# dongle.net
KiCad netlist of a schematic drawn in EAGLE
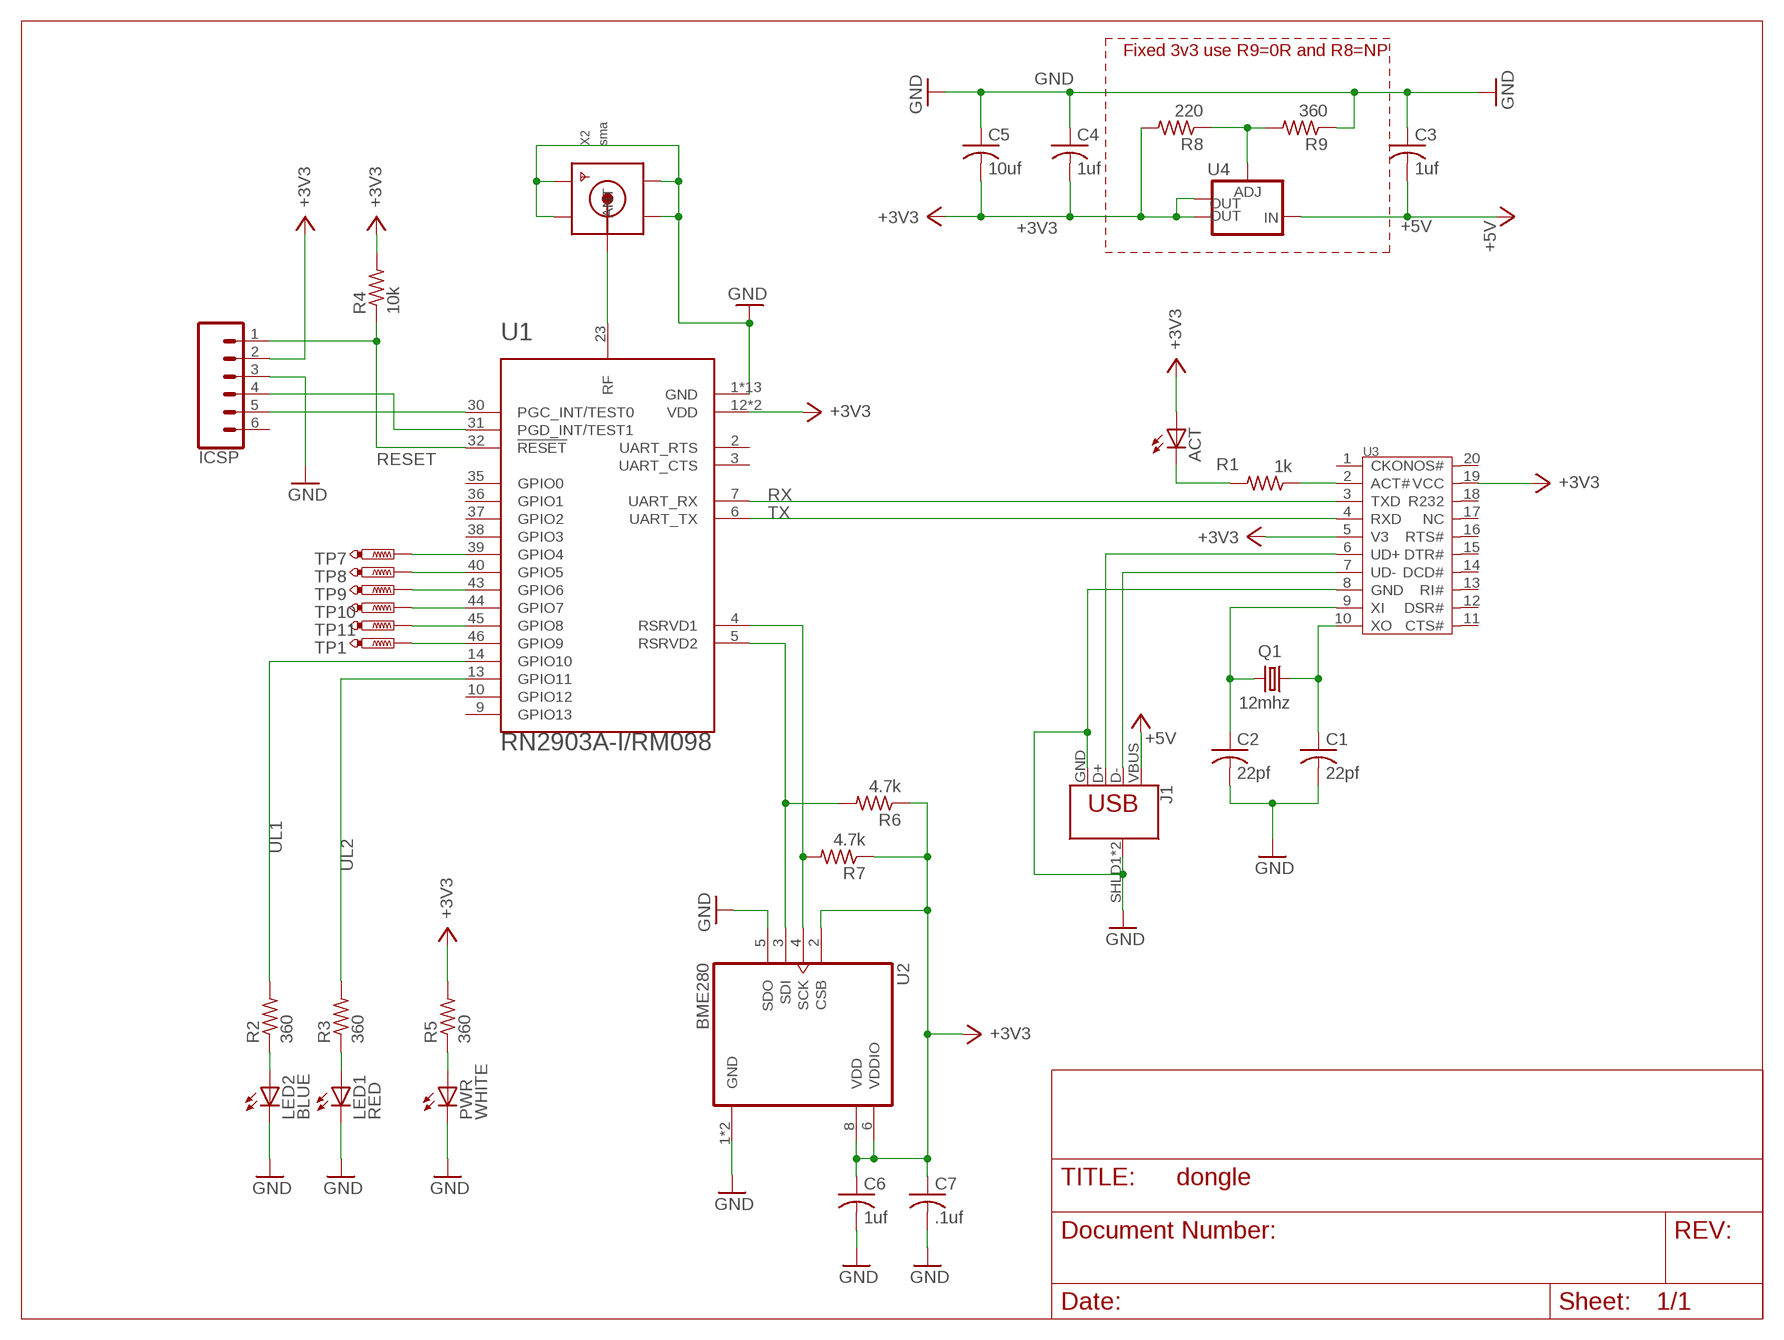
[diagram p0: schematic, sheet 1]

(export (version "E")
  (design (tool "Eeschema 10.0.6"))
  (components
    (comp (ref "ACT")
      (value "LEDCHIP-LED0603")
      (footprint "eagle-import:CHIP-LED0603")
      (libsource (lib "eagle-import") (part "LEDCHIP-LED0603"))
    )
    (comp (ref "C1")
      (value "22pf")
      (footprint "eagle-import:C0603K")
      (libsource (lib "eagle-import") (part "C-USC0603K"))
    )
    (comp (ref "C2")
      (value "22pf")
      (footprint "eagle-import:C0603K")
      (libsource (lib "eagle-import") (part "C-USC0603K"))
    )
    (comp (ref "C3")
      (value "1uf")
      (footprint "eagle-import:C0603K")
      (libsource (lib "eagle-import") (part "C-USC0603K"))
    )
    (comp (ref "C4")
      (value "1uf")
      (footprint "eagle-import:C0603K")
      (libsource (lib "eagle-import") (part "C-USC0603K"))
    )
    (comp (ref "C5")
      (value "10uf")
      (footprint "eagle-import:C1206K")
      (libsource (lib "eagle-import") (part "resistor_348_C-USC1206K"))
    )
    (comp (ref "C6")
      (value "1uf")
      (footprint "eagle-import:C0603K")
      (libsource (lib "eagle-import") (part "C-USC0603K"))
    )
    (comp (ref "C7")
      (value ".1uf")
      (footprint "eagle-import:C0603K")
      (libsource (lib "eagle-import") (part "C-USC0603K"))
    )
    (comp (ref "ICSP")
      (value "CONN_06SMD-FEMALE-V2")
      (footprint "eagle-import:1X06-SMD-FEMALE")
      (libsource (lib "eagle-import") (part "CONN_06SMD-FEMALE-V2"))
    )
    (comp (ref "J1")
      (value "USB_A_PTH_MALE")
      (footprint "eagle-import:USB-A-H")
      (libsource (lib "eagle-import") (part "USB_A_PTH_MALE"))
    )
    (comp (ref "LED1")
      (value "RED")
      (footprint "eagle-import:CHIP-LED0603")
      (libsource (lib "eagle-import") (part "LEDCHIP-LED0603"))
    )
    (comp (ref "LED2")
      (value "BLUE")
      (footprint "eagle-import:CHIP-LED0603")
      (libsource (lib "eagle-import") (part "LEDCHIP-LED0603"))
    )
    (comp (ref "PWR")
      (value "WHITE")
      (footprint "eagle-import:CHIP-LED0603")
      (libsource (lib "eagle-import") (part "LEDCHIP-LED0603"))
    )
    (comp (ref "Q1")
      (value "12mhz")
      (footprint "eagle-import:SM49")
      (libsource (lib "eagle-import") (part "CRYSTALSM49"))
    )
    (comp (ref "R1")
      (value "1k")
      (footprint "eagle-import:R0603")
      (libsource (lib "eagle-import") (part "R-US_R0603"))
    )
    (comp (ref "R2")
      (value "360")
      (footprint "eagle-import:R0603")
      (libsource (lib "eagle-import") (part "R-US_R0603"))
    )
    (comp (ref "R3")
      (value "360")
      (footprint "eagle-import:R0603")
      (libsource (lib "eagle-import") (part "R-US_R0603"))
    )
    (comp (ref "R4")
      (value "10k")
      (footprint "eagle-import:R0603")
      (libsource (lib "eagle-import") (part "R-US_R0603"))
    )
    (comp (ref "R5")
      (value "360")
      (footprint "eagle-import:R0603")
      (libsource (lib "eagle-import") (part "R-US_R0603"))
    )
    (comp (ref "R6")
      (value "4.7k")
      (footprint "eagle-import:R0603")
      (libsource (lib "eagle-import") (part "R-US_R0603"))
    )
    (comp (ref "R7")
      (value "4.7k")
      (footprint "eagle-import:R0603")
      (libsource (lib "eagle-import") (part "R-US_R0603"))
    )
    (comp (ref "R8")
      (value "220")
      (footprint "eagle-import:R0603")
      (libsource (lib "eagle-import") (part "R-US_R0603"))
    )
    (comp (ref "R9")
      (value "360")
      (footprint "eagle-import:R0603")
      (libsource (lib "eagle-import") (part "R-US_R0603"))
    )
    (comp (ref "TP1")
      (value "PTR1B1,27")
      (footprint "eagle-import:B1,27")
      (libsource (lib "eagle-import") (part "PTR1B1,27"))
    )
    (comp (ref "TP7")
      (value "PTR1B1,27")
      (footprint "eagle-import:B1,27")
      (libsource (lib "eagle-import") (part "PTR1B1,27"))
    )
    (comp (ref "TP8")
      (value "PTR1B1,27")
      (footprint "eagle-import:B1,27")
      (libsource (lib "eagle-import") (part "PTR1B1,27"))
    )
    (comp (ref "TP9")
      (value "PTR1B1,27")
      (footprint "eagle-import:B1,27")
      (libsource (lib "eagle-import") (part "PTR1B1,27"))
    )
    (comp (ref "TP10")
      (value "PTR1B1,27")
      (footprint "eagle-import:B1,27")
      (libsource (lib "eagle-import") (part "PTR1B1,27"))
    )
    (comp (ref "TP11")
      (value "PTR1B1,27")
      (footprint "eagle-import:B1,27")
      (libsource (lib "eagle-import") (part "PTR1B1,27"))
    )
    (comp (ref "U1")
      (value "RN2903A-I/RM098")
      (footprint "eagle-import:XCVR_RN2903A-I_RM098")
      (fields (field (name "MF") "Microchip"))
      (libsource (lib "eagle-import") (part "RN2903A-I/RM098"))
    )
    (comp (ref "U2")
      (value "BME280")
      (footprint "eagle-import:PSON65P250X250X100-8N")
      (fields (field (name "DIGI-KEY_PART_NUMBER") "828-1063-1-ND") (field (name "MF") "Bosch"))
      (libsource (lib "eagle-import") (part "BME280"))
    )
    (comp (ref "U3")
      (value "INTERFACE-CH340T(SSOP20)")
      (footprint "eagle-import:SSOP20-0.65-7.6X5.2MM")
      (fields (field (name "MF") "Nanjing QinHeng Electronics") (field (name "MP") "CH340T"))
      (libsource (lib "eagle-import") (part "INTERFACE-CH340T(SSOP20)"))
    )
    (comp (ref "U4")
      (value "V_REG_LM1117SOT223")
      (footprint "eagle-import:SOT223")
      (libsource (lib "eagle-import") (part "V_REG_LM1117SOT223"))
    )
    (comp (ref "X2")
      (value "sma")
      (footprint "eagle-import:SMA_EDGELAUNCH")
      (libsource (lib "eagle-import") (part "SMACONNECTOR_EDGE"))
    )
  )
  (nets
    (net (code "1") (name "+3V3") (class "Default")
      (node (ref "ACT") (pin "A") (pinfunction "A_A") (pintype "passive"))
      (node (ref "C4") (pin "2") (pinfunction "2_2") (pintype "passive"))
      (node (ref "C5") (pin "2") (pinfunction "2_2") (pintype "passive"))
      (node (ref "C6") (pin "1") (pinfunction "1_1") (pintype "passive"))
      (node (ref "C7") (pin "1") (pinfunction "1_1") (pintype "passive"))
      (node (ref "ICSP") (pin "2") (pinfunction "2_2") (pintype "passive"))
      (node (ref "R4") (pin "2") (pinfunction "2_2") (pintype "passive"))
      (node (ref "R5") (pin "2") (pinfunction "2_2") (pintype "passive"))
      (node (ref "R6") (pin "1") (pinfunction "1_1") (pintype "passive"))
      (node (ref "R7") (pin "1") (pinfunction "1_1") (pintype "passive"))
      (node (ref "R8") (pin "2") (pinfunction "2_2") (pintype "passive"))
      (node (ref "U1") (pin "12") (pinfunction "VDD_12") (pintype "power_in"))
      (node (ref "U1") (pin "34") (pinfunction "VDD_34") (pintype "power_in"))
      (node (ref "U2") (pin "2") (pinfunction "CSB_2") (pintype "input"))
      (node (ref "U2") (pin "6") (pinfunction "VDDIO_6") (pintype "power_in"))
      (node (ref "U2") (pin "8") (pinfunction "VDD_8") (pintype "power_in"))
      (node (ref "U3") (pin "19") (pinfunction "VCC_19") (pintype "power_in"))
      (node (ref "U3") (pin "5") (pinfunction "V3_5") (pintype "power_in"))
      (node (ref "U4") (pin "2") (pinfunction "OUT_2") (pintype "output"))
      (node (ref "U4") (pin "4") (pinfunction "OUT_4") (pintype "output"))
    )
    (net (code "2") (name "+5V") (class "Default")
      (node (ref "C3") (pin "2") (pinfunction "2_2") (pintype "passive"))
      (node (ref "J1") (pin "VBUS") (pinfunction "VBUS_VBUS") (pintype "power_in"))
      (node (ref "U4") (pin "3") (pinfunction "IN_3") (pintype "input"))
    )
    (net (code "3") (name "/NOS#") (class "Default")
      (node (ref "U3") (pin "20") (pinfunction "NOS#_20") (pintype "power_in"))
    )
    (net (code "4") (name "/RESET") (class "Default")
      (node (ref "ICSP") (pin "1") (pinfunction "1_1") (pintype "passive"))
      (node (ref "R4") (pin "1") (pinfunction "1_1") (pintype "passive"))
      (node (ref "U1") (pin "32") (pinfunction "~{RESET}_32") (pintype "input"))
    )
    (net (code "5") (name "/RX") (class "Default")
      (node (ref "U1") (pin "7") (pinfunction "UART_RX_7") (pintype "input"))
      (node (ref "U3") (pin "3") (pinfunction "TXD_3") (pintype "output"))
    )
    (net (code "6") (name "/TX") (class "Default")
      (node (ref "U1") (pin "6") (pinfunction "UART_TX_6") (pintype "output"))
      (node (ref "U3") (pin "4") (pinfunction "RXD_4") (pintype "input"))
    )
    (net (code "7") (name "/UL1") (class "Default")
      (node (ref "R2") (pin "2") (pinfunction "2_2") (pintype "passive"))
      (node (ref "U1") (pin "14") (pinfunction "GPIO10_14") (pintype "bidirectional"))
    )
    (net (code "8") (name "/UL2") (class "Default")
      (node (ref "R3") (pin "2") (pinfunction "2_2") (pintype "passive"))
      (node (ref "U1") (pin "13") (pinfunction "GPIO11_13") (pintype "bidirectional"))
    )
    (net (code "9") (name "GND") (class "Default")
      (node (ref "C1") (pin "2") (pinfunction "2_2") (pintype "passive"))
      (node (ref "C2") (pin "2") (pinfunction "2_2") (pintype "passive"))
      (node (ref "C3") (pin "1") (pinfunction "1_1") (pintype "passive"))
      (node (ref "C4") (pin "1") (pinfunction "1_1") (pintype "passive"))
      (node (ref "C5") (pin "1") (pinfunction "1_1") (pintype "passive"))
      (node (ref "C6") (pin "2") (pinfunction "2_2") (pintype "passive"))
      (node (ref "C7") (pin "2") (pinfunction "2_2") (pintype "passive"))
      (node (ref "ICSP") (pin "3") (pinfunction "3_3") (pintype "passive"))
      (node (ref "J1") (pin "GND") (pinfunction "GND_GND") (pintype "power_in"))
      (node (ref "J1") (pin "SHLD1") (pinfunction "SHIELD_SHLD1") (pintype "bidirectional"))
      (node (ref "J1") (pin "SHLD2") (pinfunction "SHIELD_SHLD2") (pintype "bidirectional"))
      (node (ref "LED1") (pin "C") (pinfunction "C_C") (pintype "passive"))
      (node (ref "LED2") (pin "C") (pinfunction "C_C") (pintype "passive"))
      (node (ref "PWR") (pin "C") (pinfunction "C_C") (pintype "passive"))
      (node (ref "R9") (pin "1") (pinfunction "1_1") (pintype "passive"))
      (node (ref "U1") (pin "1") (pinfunction "GND_1") (pintype "power_in"))
      (node (ref "U1") (pin "11") (pinfunction "GND_11") (pintype "power_in"))
      (node (ref "U1") (pin "20") (pinfunction "GND_20") (pintype "power_in"))
      (node (ref "U1") (pin "21") (pinfunction "GND_21") (pintype "power_in"))
      (node (ref "U1") (pin "22") (pinfunction "GND_22") (pintype "power_in"))
      (node (ref "U1") (pin "24") (pinfunction "GND_24") (pintype "power_in"))
      (node (ref "U1") (pin "26") (pinfunction "GND_26") (pintype "power_in"))
      (node (ref "U1") (pin "27") (pinfunction "GND_27") (pintype "power_in"))
      (node (ref "U1") (pin "28") (pinfunction "GND_28") (pintype "power_in"))
      (node (ref "U1") (pin "33") (pinfunction "GND_33") (pintype "power_in"))
      (node (ref "U1") (pin "41") (pinfunction "GND_41") (pintype "power_in"))
      (node (ref "U1") (pin "47") (pinfunction "GND_47") (pintype "power_in"))
      (node (ref "U1") (pin "8") (pinfunction "GND_8") (pintype "power_in"))
      (node (ref "U2") (pin "1") (pinfunction "GND_1") (pintype "power_in"))
      (node (ref "U2") (pin "5") (pinfunction "SDO_5") (pintype "bidirectional"))
      (node (ref "U2") (pin "7") (pinfunction "GND_7") (pintype "power_in"))
      (node (ref "U3") (pin "8") (pinfunction "GND_8") (pintype "power_in"))
      (node (ref "X2") (pin "GND@1") (pinfunction "GND4_GND@1") (pintype "power_in"))
      (node (ref "X2") (pin "GND@2") (pinfunction "GND3_GND@2") (pintype "power_in"))
      (node (ref "X2") (pin "GND@3") (pinfunction "GND2_GND@3") (pintype "power_in"))
      (node (ref "X2") (pin "GND@4") (pinfunction "GND1_GND@4") (pintype "power_in"))
    )
    (net (code "10") (name "Net-(ACT-PadC)") (class "Default")
      (node (ref "ACT") (pin "C") (pinfunction "C_C") (pintype "passive"))
      (node (ref "R1") (pin "2") (pinfunction "2_2") (pintype "passive"))
    )
    (net (code "11") (name "Net-(LED1-PadA)") (class "Default")
      (node (ref "LED1") (pin "A") (pinfunction "A_A") (pintype "passive"))
      (node (ref "R3") (pin "1") (pinfunction "1_1") (pintype "passive"))
    )
    (net (code "12") (name "Net-(LED2-PadA)") (class "Default")
      (node (ref "LED2") (pin "A") (pinfunction "A_A") (pintype "passive"))
      (node (ref "R2") (pin "1") (pinfunction "1_1") (pintype "passive"))
    )
    (net (code "13") (name "Net-(PWR-PadA)") (class "Default")
      (node (ref "PWR") (pin "A") (pinfunction "A_A") (pintype "passive"))
      (node (ref "R5") (pin "1") (pinfunction "1_1") (pintype "passive"))
    )
    (net (code "14") (name "Net-(U1-GPIO4)") (class "Default")
      (node (ref "TP7") (pin "TP") (pinfunction "TP_TP") (pintype "input"))
      (node (ref "U1") (pin "39") (pinfunction "GPIO4_39") (pintype "bidirectional"))
    )
    (net (code "15") (name "Net-(U1-GPIO5)") (class "Default")
      (node (ref "TP8") (pin "TP") (pinfunction "TP_TP") (pintype "input"))
      (node (ref "U1") (pin "40") (pinfunction "GPIO5_40") (pintype "bidirectional"))
    )
    (net (code "16") (name "Net-(U1-GPIO6)") (class "Default")
      (node (ref "TP9") (pin "TP") (pinfunction "TP_TP") (pintype "input"))
      (node (ref "U1") (pin "43") (pinfunction "GPIO6_43") (pintype "bidirectional"))
    )
    (net (code "17") (name "Net-(U1-GPIO7)") (class "Default")
      (node (ref "TP10") (pin "TP") (pinfunction "TP_TP") (pintype "input"))
      (node (ref "U1") (pin "44") (pinfunction "GPIO7_44") (pintype "bidirectional"))
    )
    (net (code "18") (name "Net-(U1-GPIO8)") (class "Default")
      (node (ref "TP11") (pin "TP") (pinfunction "TP_TP") (pintype "input"))
      (node (ref "U1") (pin "45") (pinfunction "GPIO8_45") (pintype "bidirectional"))
    )
    (net (code "19") (name "Net-(U1-GPIO9)") (class "Default")
      (node (ref "TP1") (pin "TP") (pinfunction "TP_TP") (pintype "input"))
      (node (ref "U1") (pin "46") (pinfunction "GPIO9_46") (pintype "bidirectional"))
    )
    (net (code "20") (name "Net-(U1-PGC_INT{slash}TEST0)") (class "Default")
      (node (ref "ICSP") (pin "5") (pinfunction "5_5") (pintype "passive"))
      (node (ref "U1") (pin "30") (pinfunction "PGC_INT/TEST0_30") (pintype "passive"))
    )
    (net (code "21") (name "Net-(U1-PGD_INT{slash}TEST1)") (class "Default")
      (node (ref "ICSP") (pin "4") (pinfunction "4_4") (pintype "passive"))
      (node (ref "U1") (pin "31") (pinfunction "PGD_INT/TEST1_31") (pintype "passive"))
    )
    (net (code "22") (name "Net-(U1-RF)") (class "Default")
      (node (ref "U1") (pin "23") (pinfunction "RF_23") (pintype "passive"))
      (node (ref "X2") (pin "P") (pinfunction "ANT_P") (pintype "bidirectional"))
    )
    (net (code "23") (name "Net-(U1-RSRVD1)") (class "Default")
      (node (ref "R7") (pin "2") (pinfunction "2_2") (pintype "passive"))
      (node (ref "U1") (pin "4") (pinfunction "RSRVD1_4") (pintype "passive"))
      (node (ref "U2") (pin "4") (pinfunction "SCK_4") (pintype "input"))
    )
    (net (code "24") (name "Net-(U1-RSRVD2)") (class "Default")
      (node (ref "R6") (pin "2") (pinfunction "2_2") (pintype "passive"))
      (node (ref "U1") (pin "5") (pinfunction "RSRVD2_5") (pintype "passive"))
      (node (ref "U2") (pin "3") (pinfunction "SDI_3") (pintype "bidirectional"))
    )
    (net (code "25") (name "Net-(U3-ACT#)") (class "Default")
      (node (ref "R1") (pin "1") (pinfunction "1_1") (pintype "passive"))
      (node (ref "U3") (pin "2") (pinfunction "ACT#_2") (pintype "output"))
    )
    (net (code "26") (name "Net-(U3-UD+)") (class "Default")
      (node (ref "J1") (pin "D+") (pinfunction "D+_D+") (pintype "bidirectional"))
      (node (ref "U3") (pin "6") (pinfunction "UD+_6") (pintype "bidirectional"))
    )
    (net (code "27") (name "Net-(U3-UD-)") (class "Default")
      (node (ref "J1") (pin "D-") (pinfunction "D-_D-") (pintype "bidirectional"))
      (node (ref "U3") (pin "7") (pinfunction "UD-_7") (pintype "bidirectional"))
    )
    (net (code "28") (name "Net-(U3-XI)") (class "Default")
      (node (ref "C2") (pin "1") (pinfunction "1_1") (pintype "passive"))
      (node (ref "Q1") (pin "2") (pinfunction "2_2") (pintype "passive"))
      (node (ref "U3") (pin "9") (pinfunction "XI_9") (pintype "input"))
    )
    (net (code "29") (name "Net-(U3-XO)") (class "Default")
      (node (ref "C1") (pin "1") (pinfunction "1_1") (pintype "passive"))
      (node (ref "Q1") (pin "1") (pinfunction "1_1") (pintype "passive"))
      (node (ref "U3") (pin "10") (pinfunction "XO_10") (pintype "output"))
    )
    (net (code "30") (name "Net-(U4-ADJ)") (class "Default")
      (node (ref "R8") (pin "1") (pinfunction "1_1") (pintype "passive"))
      (node (ref "R9") (pin "2") (pinfunction "2_2") (pintype "passive"))
      (node (ref "U4") (pin "1") (pinfunction "ADJ_1") (pintype "input"))
    )
    (net (code "31") (name "unconnected-(ICSP-Pad6)") (class "Default")
      (node (ref "ICSP") (pin "6") (pinfunction "6_6") (pintype "passive"))
    )
    (net (code "32") (name "unconnected-(U1-GPIO0-Pad35)") (class "Default")
      (node (ref "U1") (pin "35") (pinfunction "GPIO0_35") (pintype "bidirectional"))
    )
    (net (code "33") (name "unconnected-(U1-GPIO1-Pad36)") (class "Default")
      (node (ref "U1") (pin "36") (pinfunction "GPIO1_36") (pintype "bidirectional"))
    )
    (net (code "34") (name "unconnected-(U1-GPIO2-Pad37)") (class "Default")
      (node (ref "U1") (pin "37") (pinfunction "GPIO2_37") (pintype "bidirectional"))
    )
    (net (code "35") (name "unconnected-(U1-GPIO3-Pad38)") (class "Default")
      (node (ref "U1") (pin "38") (pinfunction "GPIO3_38") (pintype "bidirectional"))
    )
    (net (code "36") (name "unconnected-(U1-GPIO12-Pad10)") (class "Default")
      (node (ref "U1") (pin "10") (pinfunction "GPIO12_10") (pintype "bidirectional"))
    )
    (net (code "37") (name "unconnected-(U1-GPIO13-Pad9)") (class "Default")
      (node (ref "U1") (pin "9") (pinfunction "GPIO13_9") (pintype "bidirectional"))
    )
    (net (code "38") (name "unconnected-(U1-UART_CTS-Pad3)") (class "Default")
      (node (ref "U1") (pin "3") (pinfunction "UART_CTS_3") (pintype "input"))
    )
    (net (code "39") (name "unconnected-(U1-UART_RTS-Pad2)") (class "Default")
      (node (ref "U1") (pin "2") (pinfunction "UART_RTS_2") (pintype "output"))
    )
    (net (code "40") (name "unconnected-(U3-CKO-Pad1)") (class "Default")
      (node (ref "U3") (pin "1") (pinfunction "CKO_1") (pintype "output"))
    )
    (net (code "41") (name "unconnected-(U3-CTS#-Pad11)") (class "Default")
      (node (ref "U3") (pin "11") (pinfunction "CTS#_11") (pintype "input"))
    )
    (net (code "42") (name "unconnected-(U3-DCD#-Pad14)") (class "Default")
      (node (ref "U3") (pin "14") (pinfunction "DCD#_14") (pintype "input"))
    )
    (net (code "43") (name "unconnected-(U3-DSR#-Pad12)") (class "Default")
      (node (ref "U3") (pin "12") (pinfunction "DSR#_12") (pintype "input"))
    )
    (net (code "44") (name "unconnected-(U3-DTR#-Pad15)") (class "Default")
      (node (ref "U3") (pin "15") (pinfunction "DTR#_15") (pintype "output"))
    )
    (net (code "45") (name "unconnected-(U3-NC-Pad17)") (class "Default")
      (node (ref "U3") (pin "17") (pinfunction "NC_17") (pintype "no_connect"))
    )
    (net (code "46") (name "unconnected-(U3-R232-Pad18)") (class "Default")
      (node (ref "U3") (pin "18") (pinfunction "R232_18") (pintype "input"))
    )
    (net (code "47") (name "unconnected-(U3-RI#-Pad13)") (class "Default")
      (node (ref "U3") (pin "13") (pinfunction "RI#_13") (pintype "input"))
    )
    (net (code "48") (name "unconnected-(U3-RTS#-Pad16)") (class "Default")
      (node (ref "U3") (pin "16") (pinfunction "RTS#_16") (pintype "output"))
    )
  )
)
